# MainBoard.net
KiCad netlist of a schematic drawn in EAGLE
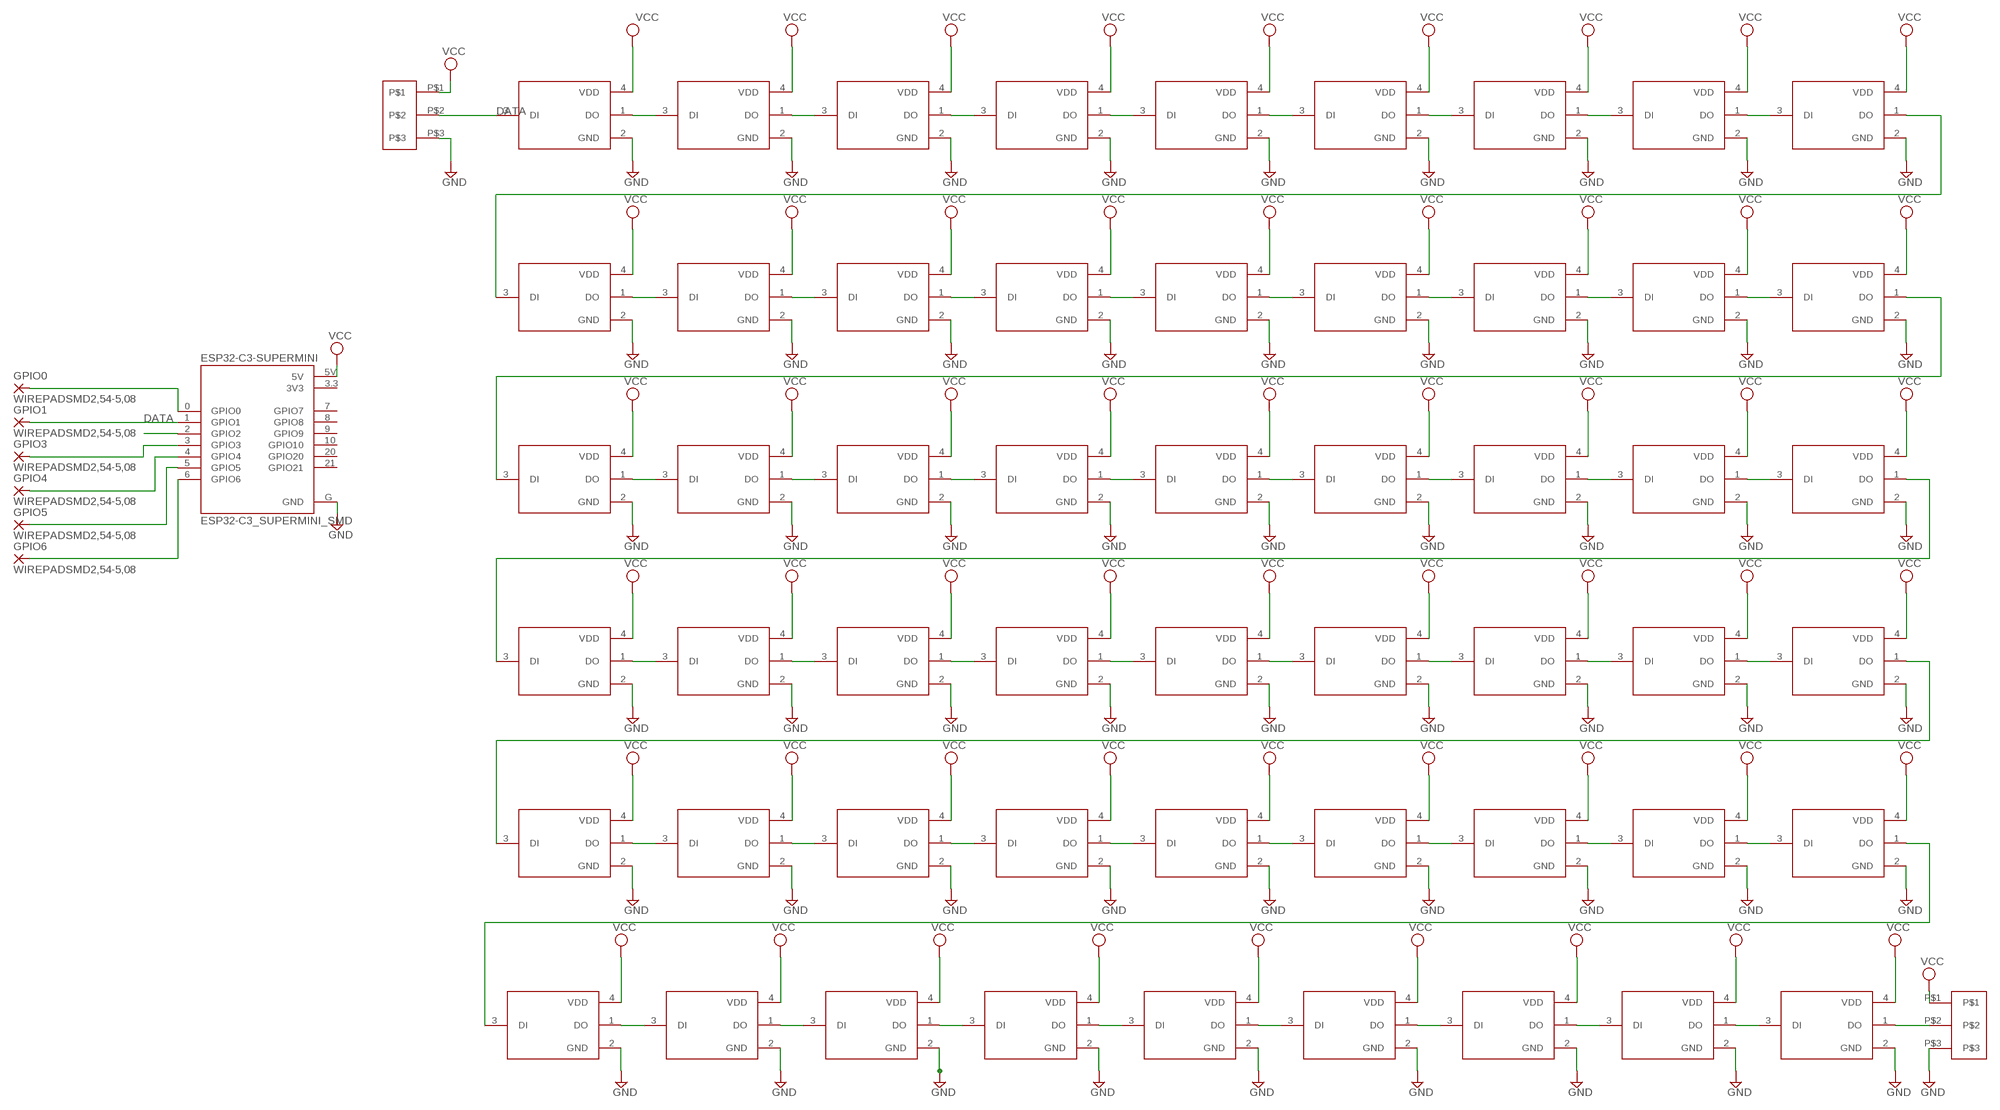
[diagram p0: schematic, sheet 1]

(export (version "E")
  (design (tool "Eeschema 10.0.6"))
  (components
    (comp (ref "ESP32-C3-SUPERMINI")
      (value "ESP32-C3_SUPERMINI_SMD")
      (footprint "eagle-import:MODULE_ESP32-C3_SUPERMINI")
      (fields (field (name "MF") "Espressif Systems") (field (name "MP") "ESP32-C3 SuperMini_SMD"))
      (libsource (lib "eagle-import") (part "ESP32-C3_SUPERMINI_SMD"))
    )
    (comp (ref "GPIO0")
      (value "WIREPADSMD2,54-5,08")
      (footprint "eagle-import:SMD2,54-5,08")
      (libsource (lib "eagle-import") (part "WIREPADSMD2,54-5,08"))
    )
    (comp (ref "GPIO1")
      (value "WIREPADSMD2,54-5,08")
      (footprint "eagle-import:SMD2,54-5,08")
      (libsource (lib "eagle-import") (part "WIREPADSMD2,54-5,08"))
    )
    (comp (ref "GPIO3")
      (value "WIREPADSMD2,54-5,08")
      (footprint "eagle-import:SMD2,54-5,08")
      (libsource (lib "eagle-import") (part "WIREPADSMD2,54-5,08"))
    )
    (comp (ref "GPIO4")
      (value "WIREPADSMD2,54-5,08")
      (footprint "eagle-import:SMD2,54-5,08")
      (libsource (lib "eagle-import") (part "WIREPADSMD2,54-5,08"))
    )
    (comp (ref "GPIO5")
      (value "WIREPADSMD2,54-5,08")
      (footprint "eagle-import:SMD2,54-5,08")
      (libsource (lib "eagle-import") (part "WIREPADSMD2,54-5,08"))
    )
    (comp (ref "GPIO6")
      (value "WIREPADSMD2,54-5,08")
      (footprint "eagle-import:SMD2,54-5,08")
      (libsource (lib "eagle-import") (part "WIREPADSMD2,54-5,08"))
    )
    (comp (ref "LED1")
      (value "WS2812B2020")
      (footprint "eagle-import:LED_WS2812B2020")
      (fields (field (name "MF") "WorldSemi"))
      (libsource (lib "eagle-import") (part "WS2812B2020"))
    )
    (comp (ref "LED2")
      (value "WS2812B2020")
      (footprint "eagle-import:LED_WS2812B2020")
      (fields (field (name "MF") "WorldSemi"))
      (libsource (lib "eagle-import") (part "WS2812B2020"))
    )
    (comp (ref "LED3")
      (value "WS2812B2020")
      (footprint "eagle-import:LED_WS2812B2020")
      (fields (field (name "MF") "WorldSemi"))
      (libsource (lib "eagle-import") (part "WS2812B2020"))
    )
    (comp (ref "LED4")
      (value "WS2812B2020")
      (footprint "eagle-import:LED_WS2812B2020")
      (fields (field (name "MF") "WorldSemi"))
      (libsource (lib "eagle-import") (part "WS2812B2020"))
    )
    (comp (ref "LED5")
      (value "WS2812B2020")
      (footprint "eagle-import:LED_WS2812B2020")
      (fields (field (name "MF") "WorldSemi"))
      (libsource (lib "eagle-import") (part "WS2812B2020"))
    )
    (comp (ref "LED6")
      (value "WS2812B2020")
      (footprint "eagle-import:LED_WS2812B2020")
      (fields (field (name "MF") "WorldSemi"))
      (libsource (lib "eagle-import") (part "WS2812B2020"))
    )
    (comp (ref "LED7")
      (value "WS2812B2020")
      (footprint "eagle-import:LED_WS2812B2020")
      (fields (field (name "MF") "WorldSemi"))
      (libsource (lib "eagle-import") (part "WS2812B2020"))
    )
    (comp (ref "LED8")
      (value "WS2812B2020")
      (footprint "eagle-import:LED_WS2812B2020")
      (fields (field (name "MF") "WorldSemi"))
      (libsource (lib "eagle-import") (part "WS2812B2020"))
    )
    (comp (ref "LED9")
      (value "WS2812B2020")
      (footprint "eagle-import:LED_WS2812B2020")
      (fields (field (name "MF") "WorldSemi"))
      (libsource (lib "eagle-import") (part "WS2812B2020"))
    )
    (comp (ref "LED10")
      (value "WS2812B2020")
      (footprint "eagle-import:LED_WS2812B2020")
      (fields (field (name "MF") "WorldSemi"))
      (libsource (lib "eagle-import") (part "WS2812B2020"))
    )
    (comp (ref "LED11")
      (value "WS2812B2020")
      (footprint "eagle-import:LED_WS2812B2020")
      (fields (field (name "MF") "WorldSemi"))
      (libsource (lib "eagle-import") (part "WS2812B2020"))
    )
    (comp (ref "LED12")
      (value "WS2812B2020")
      (footprint "eagle-import:LED_WS2812B2020")
      (fields (field (name "MF") "WorldSemi"))
      (libsource (lib "eagle-import") (part "WS2812B2020"))
    )
    (comp (ref "LED13")
      (value "WS2812B2020")
      (footprint "eagle-import:LED_WS2812B2020")
      (fields (field (name "MF") "WorldSemi"))
      (libsource (lib "eagle-import") (part "WS2812B2020"))
    )
    (comp (ref "LED14")
      (value "WS2812B2020")
      (footprint "eagle-import:LED_WS2812B2020")
      (fields (field (name "MF") "WorldSemi"))
      (libsource (lib "eagle-import") (part "WS2812B2020"))
    )
    (comp (ref "LED15")
      (value "WS2812B2020")
      (footprint "eagle-import:LED_WS2812B2020")
      (fields (field (name "MF") "WorldSemi"))
      (libsource (lib "eagle-import") (part "WS2812B2020"))
    )
    (comp (ref "LED16")
      (value "WS2812B2020")
      (footprint "eagle-import:LED_WS2812B2020")
      (fields (field (name "MF") "WorldSemi"))
      (libsource (lib "eagle-import") (part "WS2812B2020"))
    )
    (comp (ref "LED17")
      (value "WS2812B2020")
      (footprint "eagle-import:LED_WS2812B2020")
      (fields (field (name "MF") "WorldSemi"))
      (libsource (lib "eagle-import") (part "WS2812B2020"))
    )
    (comp (ref "LED18")
      (value "WS2812B2020")
      (footprint "eagle-import:LED_WS2812B2020")
      (fields (field (name "MF") "WorldSemi"))
      (libsource (lib "eagle-import") (part "WS2812B2020"))
    )
    (comp (ref "LED19")
      (value "WS2812B2020")
      (footprint "eagle-import:LED_WS2812B2020")
      (fields (field (name "MF") "WorldSemi"))
      (libsource (lib "eagle-import") (part "WS2812B2020"))
    )
    (comp (ref "LED20")
      (value "WS2812B2020")
      (footprint "eagle-import:LED_WS2812B2020")
      (fields (field (name "MF") "WorldSemi"))
      (libsource (lib "eagle-import") (part "WS2812B2020"))
    )
    (comp (ref "LED21")
      (value "WS2812B2020")
      (footprint "eagle-import:LED_WS2812B2020")
      (fields (field (name "MF") "WorldSemi"))
      (libsource (lib "eagle-import") (part "WS2812B2020"))
    )
    (comp (ref "LED22")
      (value "WS2812B2020")
      (footprint "eagle-import:LED_WS2812B2020")
      (fields (field (name "MF") "WorldSemi"))
      (libsource (lib "eagle-import") (part "WS2812B2020"))
    )
    (comp (ref "LED23")
      (value "WS2812B2020")
      (footprint "eagle-import:LED_WS2812B2020")
      (fields (field (name "MF") "WorldSemi"))
      (libsource (lib "eagle-import") (part "WS2812B2020"))
    )
    (comp (ref "LED24")
      (value "WS2812B2020")
      (footprint "eagle-import:LED_WS2812B2020")
      (fields (field (name "MF") "WorldSemi"))
      (libsource (lib "eagle-import") (part "WS2812B2020"))
    )
    (comp (ref "LED25")
      (value "WS2812B2020")
      (footprint "eagle-import:LED_WS2812B2020")
      (fields (field (name "MF") "WorldSemi"))
      (libsource (lib "eagle-import") (part "WS2812B2020"))
    )
    (comp (ref "LED26")
      (value "WS2812B2020")
      (footprint "eagle-import:LED_WS2812B2020")
      (fields (field (name "MF") "WorldSemi"))
      (libsource (lib "eagle-import") (part "WS2812B2020"))
    )
    (comp (ref "LED27")
      (value "WS2812B2020")
      (footprint "eagle-import:LED_WS2812B2020")
      (fields (field (name "MF") "WorldSemi"))
      (libsource (lib "eagle-import") (part "WS2812B2020"))
    )
    (comp (ref "LED28")
      (value "WS2812B2020")
      (footprint "eagle-import:LED_WS2812B2020")
      (fields (field (name "MF") "WorldSemi"))
      (libsource (lib "eagle-import") (part "WS2812B2020"))
    )
    (comp (ref "LED29")
      (value "WS2812B2020")
      (footprint "eagle-import:LED_WS2812B2020")
      (fields (field (name "MF") "WorldSemi"))
      (libsource (lib "eagle-import") (part "WS2812B2020"))
    )
    (comp (ref "LED30")
      (value "WS2812B2020")
      (footprint "eagle-import:LED_WS2812B2020")
      (fields (field (name "MF") "WorldSemi"))
      (libsource (lib "eagle-import") (part "WS2812B2020"))
    )
    (comp (ref "LED31")
      (value "WS2812B2020")
      (footprint "eagle-import:LED_WS2812B2020")
      (fields (field (name "MF") "WorldSemi"))
      (libsource (lib "eagle-import") (part "WS2812B2020"))
    )
    (comp (ref "LED32")
      (value "WS2812B2020")
      (footprint "eagle-import:LED_WS2812B2020")
      (fields (field (name "MF") "WorldSemi"))
      (libsource (lib "eagle-import") (part "WS2812B2020"))
    )
    (comp (ref "LED33")
      (value "WS2812B2020")
      (footprint "eagle-import:LED_WS2812B2020")
      (fields (field (name "MF") "WorldSemi"))
      (libsource (lib "eagle-import") (part "WS2812B2020"))
    )
    (comp (ref "LED34")
      (value "WS2812B2020")
      (footprint "eagle-import:LED_WS2812B2020")
      (fields (field (name "MF") "WorldSemi"))
      (libsource (lib "eagle-import") (part "WS2812B2020"))
    )
    (comp (ref "LED35")
      (value "WS2812B2020")
      (footprint "eagle-import:LED_WS2812B2020")
      (fields (field (name "MF") "WorldSemi"))
      (libsource (lib "eagle-import") (part "WS2812B2020"))
    )
    (comp (ref "LED36")
      (value "WS2812B2020")
      (footprint "eagle-import:LED_WS2812B2020")
      (fields (field (name "MF") "WorldSemi"))
      (libsource (lib "eagle-import") (part "WS2812B2020"))
    )
    (comp (ref "LED37")
      (value "WS2812B2020")
      (footprint "eagle-import:LED_WS2812B2020")
      (fields (field (name "MF") "WorldSemi"))
      (libsource (lib "eagle-import") (part "WS2812B2020"))
    )
    (comp (ref "LED38")
      (value "WS2812B2020")
      (footprint "eagle-import:LED_WS2812B2020")
      (fields (field (name "MF") "WorldSemi"))
      (libsource (lib "eagle-import") (part "WS2812B2020"))
    )
    (comp (ref "LED39")
      (value "WS2812B2020")
      (footprint "eagle-import:LED_WS2812B2020")
      (fields (field (name "MF") "WorldSemi"))
      (libsource (lib "eagle-import") (part "WS2812B2020"))
    )
    (comp (ref "LED40")
      (value "WS2812B2020")
      (footprint "eagle-import:LED_WS2812B2020")
      (fields (field (name "MF") "WorldSemi"))
      (libsource (lib "eagle-import") (part "WS2812B2020"))
    )
    (comp (ref "LED41")
      (value "WS2812B2020")
      (footprint "eagle-import:LED_WS2812B2020")
      (fields (field (name "MF") "WorldSemi"))
      (libsource (lib "eagle-import") (part "WS2812B2020"))
    )
    (comp (ref "LED42")
      (value "WS2812B2020")
      (footprint "eagle-import:LED_WS2812B2020")
      (fields (field (name "MF") "WorldSemi"))
      (libsource (lib "eagle-import") (part "WS2812B2020"))
    )
    (comp (ref "LED43")
      (value "WS2812B2020")
      (footprint "eagle-import:LED_WS2812B2020")
      (fields (field (name "MF") "WorldSemi"))
      (libsource (lib "eagle-import") (part "WS2812B2020"))
    )
    (comp (ref "LED44")
      (value "WS2812B2020")
      (footprint "eagle-import:LED_WS2812B2020")
      (fields (field (name "MF") "WorldSemi"))
      (libsource (lib "eagle-import") (part "WS2812B2020"))
    )
    (comp (ref "LED45")
      (value "WS2812B2020")
      (footprint "eagle-import:LED_WS2812B2020")
      (fields (field (name "MF") "WorldSemi"))
      (libsource (lib "eagle-import") (part "WS2812B2020"))
    )
    (comp (ref "LED46")
      (value "WS2812B2020")
      (footprint "eagle-import:LED_WS2812B2020")
      (fields (field (name "MF") "WorldSemi"))
      (libsource (lib "eagle-import") (part "WS2812B2020"))
    )
    (comp (ref "LED47")
      (value "WS2812B2020")
      (footprint "eagle-import:LED_WS2812B2020")
      (fields (field (name "MF") "WorldSemi"))
      (libsource (lib "eagle-import") (part "WS2812B2020"))
    )
    (comp (ref "LED48")
      (value "WS2812B2020")
      (footprint "eagle-import:LED_WS2812B2020")
      (fields (field (name "MF") "WorldSemi"))
      (libsource (lib "eagle-import") (part "WS2812B2020"))
    )
    (comp (ref "LED49")
      (value "WS2812B2020")
      (footprint "eagle-import:LED_WS2812B2020")
      (fields (field (name "MF") "WorldSemi"))
      (libsource (lib "eagle-import") (part "WS2812B2020"))
    )
    (comp (ref "LED50")
      (value "WS2812B2020")
      (footprint "eagle-import:LED_WS2812B2020")
      (fields (field (name "MF") "WorldSemi"))
      (libsource (lib "eagle-import") (part "WS2812B2020"))
    )
    (comp (ref "LED51")
      (value "WS2812B2020")
      (footprint "eagle-import:LED_WS2812B2020")
      (fields (field (name "MF") "WorldSemi"))
      (libsource (lib "eagle-import") (part "WS2812B2020"))
    )
    (comp (ref "LED52")
      (value "WS2812B2020")
      (footprint "eagle-import:LED_WS2812B2020")
      (fields (field (name "MF") "WorldSemi"))
      (libsource (lib "eagle-import") (part "WS2812B2020"))
    )
    (comp (ref "LED53")
      (value "WS2812B2020")
      (footprint "eagle-import:LED_WS2812B2020")
      (fields (field (name "MF") "WorldSemi"))
      (libsource (lib "eagle-import") (part "WS2812B2020"))
    )
    (comp (ref "LED54")
      (value "WS2812B2020")
      (footprint "eagle-import:LED_WS2812B2020")
      (fields (field (name "MF") "WorldSemi"))
      (libsource (lib "eagle-import") (part "WS2812B2020"))
    )
    (comp (ref "U$1")
      (value "POGO-3-M")
      (footprint "eagle-import:POGO-3-M")
      (libsource (lib "eagle-import") (part "POGO-3-M"))
    )
    (comp (ref "U$2")
      (value "POGO-3-F")
      (footprint "eagle-import:POGO-3-F")
      (libsource (lib "eagle-import") (part "POGO-3-F"))
    )
  )
  (nets
    (net (code "1") (name "/3V3") (class "Default")
      (node (ref "ESP32-C3-SUPERMINI") (pin "3.3") (pinfunction "3V3_3.3") (pintype "power_in"))
    )
    (net (code "2") (name "/DATA") (class "Default")
      (node (ref "ESP32-C3-SUPERMINI") (pin "2") (pinfunction "GPIO2_2") (pintype "bidirectional"))
      (node (ref "LED1") (pin "3") (pinfunction "DI_3") (pintype "input"))
      (node (ref "U$2") (pin "P$2") (pinfunction "P$2_P$2") (pintype "bidirectional"))
    )
    (net (code "3") (name "GND") (class "Default")
      (node (ref "ESP32-C3-SUPERMINI") (pin "G") (pinfunction "GND_G") (pintype "power_in"))
      (node (ref "LED1") (pin "2") (pinfunction "GND_2") (pintype "power_in"))
      (node (ref "LED10") (pin "2") (pinfunction "GND_2") (pintype "power_in"))
      (node (ref "LED11") (pin "2") (pinfunction "GND_2") (pintype "power_in"))
      (node (ref "LED12") (pin "2") (pinfunction "GND_2") (pintype "power_in"))
      (node (ref "LED13") (pin "2") (pinfunction "GND_2") (pintype "power_in"))
      (node (ref "LED14") (pin "2") (pinfunction "GND_2") (pintype "power_in"))
      (node (ref "LED15") (pin "2") (pinfunction "GND_2") (pintype "power_in"))
      (node (ref "LED16") (pin "2") (pinfunction "GND_2") (pintype "power_in"))
      (node (ref "LED17") (pin "2") (pinfunction "GND_2") (pintype "power_in"))
      (node (ref "LED18") (pin "2") (pinfunction "GND_2") (pintype "power_in"))
      (node (ref "LED19") (pin "2") (pinfunction "GND_2") (pintype "power_in"))
      (node (ref "LED2") (pin "2") (pinfunction "GND_2") (pintype "power_in"))
      (node (ref "LED20") (pin "2") (pinfunction "GND_2") (pintype "power_in"))
      (node (ref "LED21") (pin "2") (pinfunction "GND_2") (pintype "power_in"))
      (node (ref "LED22") (pin "2") (pinfunction "GND_2") (pintype "power_in"))
      (node (ref "LED23") (pin "2") (pinfunction "GND_2") (pintype "power_in"))
      (node (ref "LED24") (pin "2") (pinfunction "GND_2") (pintype "power_in"))
      (node (ref "LED25") (pin "2") (pinfunction "GND_2") (pintype "power_in"))
      (node (ref "LED26") (pin "2") (pinfunction "GND_2") (pintype "power_in"))
      (node (ref "LED27") (pin "2") (pinfunction "GND_2") (pintype "power_in"))
      (node (ref "LED28") (pin "2") (pinfunction "GND_2") (pintype "power_in"))
      (node (ref "LED29") (pin "2") (pinfunction "GND_2") (pintype "power_in"))
      (node (ref "LED3") (pin "2") (pinfunction "GND_2") (pintype "power_in"))
      (node (ref "LED30") (pin "2") (pinfunction "GND_2") (pintype "power_in"))
      (node (ref "LED31") (pin "2") (pinfunction "GND_2") (pintype "power_in"))
      (node (ref "LED32") (pin "2") (pinfunction "GND_2") (pintype "power_in"))
      (node (ref "LED33") (pin "2") (pinfunction "GND_2") (pintype "power_in"))
      (node (ref "LED34") (pin "2") (pinfunction "GND_2") (pintype "power_in"))
      (node (ref "LED35") (pin "2") (pinfunction "GND_2") (pintype "power_in"))
      (node (ref "LED36") (pin "2") (pinfunction "GND_2") (pintype "power_in"))
      (node (ref "LED37") (pin "2") (pinfunction "GND_2") (pintype "power_in"))
      (node (ref "LED38") (pin "2") (pinfunction "GND_2") (pintype "power_in"))
      (node (ref "LED39") (pin "2") (pinfunction "GND_2") (pintype "power_in"))
      (node (ref "LED4") (pin "2") (pinfunction "GND_2") (pintype "power_in"))
      (node (ref "LED40") (pin "2") (pinfunction "GND_2") (pintype "power_in"))
      (node (ref "LED41") (pin "2") (pinfunction "GND_2") (pintype "power_in"))
      (node (ref "LED42") (pin "2") (pinfunction "GND_2") (pintype "power_in"))
      (node (ref "LED43") (pin "2") (pinfunction "GND_2") (pintype "power_in"))
      (node (ref "LED44") (pin "2") (pinfunction "GND_2") (pintype "power_in"))
      (node (ref "LED45") (pin "2") (pinfunction "GND_2") (pintype "power_in"))
      (node (ref "LED46") (pin "2") (pinfunction "GND_2") (pintype "power_in"))
      (node (ref "LED47") (pin "2") (pinfunction "GND_2") (pintype "power_in"))
      (node (ref "LED48") (pin "2") (pinfunction "GND_2") (pintype "power_in"))
      (node (ref "LED49") (pin "2") (pinfunction "GND_2") (pintype "power_in"))
      (node (ref "LED5") (pin "2") (pinfunction "GND_2") (pintype "power_in"))
      (node (ref "LED50") (pin "2") (pinfunction "GND_2") (pintype "power_in"))
      (node (ref "LED51") (pin "2") (pinfunction "GND_2") (pintype "power_in"))
      (node (ref "LED52") (pin "2") (pinfunction "GND_2") (pintype "power_in"))
      (node (ref "LED53") (pin "2") (pinfunction "GND_2") (pintype "power_in"))
      (node (ref "LED54") (pin "2") (pinfunction "GND_2") (pintype "power_in"))
      (node (ref "LED6") (pin "2") (pinfunction "GND_2") (pintype "power_in"))
      (node (ref "LED7") (pin "2") (pinfunction "GND_2") (pintype "power_in"))
      (node (ref "LED8") (pin "2") (pinfunction "GND_2") (pintype "power_in"))
      (node (ref "LED9") (pin "2") (pinfunction "GND_2") (pintype "power_in"))
      (node (ref "U$1") (pin "P$3") (pinfunction "P$3_P$3") (pintype "bidirectional"))
      (node (ref "U$2") (pin "P$3") (pinfunction "P$3_P$3") (pintype "bidirectional"))
    )
    (net (code "4") (name "Net-(ESP32-C3-SUPERMINI-GPIO0)") (class "Default")
      (node (ref "ESP32-C3-SUPERMINI") (pin "0") (pinfunction "GPIO0_0") (pintype "bidirectional"))
      (node (ref "GPIO0") (pin "1") (pinfunction "P_1") (pintype "passive"))
    )
    (net (code "5") (name "Net-(ESP32-C3-SUPERMINI-GPIO1)") (class "Default")
      (node (ref "ESP32-C3-SUPERMINI") (pin "1") (pinfunction "GPIO1_1") (pintype "bidirectional"))
      (node (ref "GPIO1") (pin "1") (pinfunction "P_1") (pintype "passive"))
    )
    (net (code "6") (name "Net-(ESP32-C3-SUPERMINI-GPIO3)") (class "Default")
      (node (ref "ESP32-C3-SUPERMINI") (pin "3") (pinfunction "GPIO3_3") (pintype "bidirectional"))
      (node (ref "GPIO3") (pin "1") (pinfunction "P_1") (pintype "passive"))
    )
    (net (code "7") (name "Net-(ESP32-C3-SUPERMINI-GPIO4)") (class "Default")
      (node (ref "ESP32-C3-SUPERMINI") (pin "4") (pinfunction "GPIO4_4") (pintype "bidirectional"))
      (node (ref "GPIO4") (pin "1") (pinfunction "P_1") (pintype "passive"))
    )
    (net (code "8") (name "Net-(ESP32-C3-SUPERMINI-GPIO5)") (class "Default")
      (node (ref "ESP32-C3-SUPERMINI") (pin "5") (pinfunction "GPIO5_5") (pintype "bidirectional"))
      (node (ref "GPIO5") (pin "1") (pinfunction "P_1") (pintype "passive"))
    )
    (net (code "9") (name "Net-(ESP32-C3-SUPERMINI-GPIO6)") (class "Default")
      (node (ref "ESP32-C3-SUPERMINI") (pin "6") (pinfunction "GPIO6_6") (pintype "bidirectional"))
      (node (ref "GPIO6") (pin "1") (pinfunction "P_1") (pintype "passive"))
    )
    (net (code "10") (name "Net-(LED1-DO)") (class "Default")
      (node (ref "LED1") (pin "1") (pinfunction "DO_1") (pintype "output"))
      (node (ref "LED2") (pin "3") (pinfunction "DI_3") (pintype "input"))
    )
    (net (code "11") (name "Net-(LED2-DO)") (class "Default")
      (node (ref "LED2") (pin "1") (pinfunction "DO_1") (pintype "output"))
      (node (ref "LED3") (pin "3") (pinfunction "DI_3") (pintype "input"))
    )
    (net (code "12") (name "Net-(LED3-DO)") (class "Default")
      (node (ref "LED3") (pin "1") (pinfunction "DO_1") (pintype "output"))
      (node (ref "LED4") (pin "3") (pinfunction "DI_3") (pintype "input"))
    )
    (net (code "13") (name "Net-(LED4-DO)") (class "Default")
      (node (ref "LED4") (pin "1") (pinfunction "DO_1") (pintype "output"))
      (node (ref "LED5") (pin "3") (pinfunction "DI_3") (pintype "input"))
    )
    (net (code "14") (name "Net-(LED5-DO)") (class "Default")
      (node (ref "LED5") (pin "1") (pinfunction "DO_1") (pintype "output"))
      (node (ref "LED6") (pin "3") (pinfunction "DI_3") (pintype "input"))
    )
    (net (code "15") (name "Net-(LED6-DO)") (class "Default")
      (node (ref "LED6") (pin "1") (pinfunction "DO_1") (pintype "output"))
      (node (ref "LED7") (pin "3") (pinfunction "DI_3") (pintype "input"))
    )
    (net (code "16") (name "Net-(LED7-DO)") (class "Default")
      (node (ref "LED7") (pin "1") (pinfunction "DO_1") (pintype "output"))
      (node (ref "LED8") (pin "3") (pinfunction "DI_3") (pintype "input"))
    )
    (net (code "17") (name "Net-(LED8-DO)") (class "Default")
      (node (ref "LED8") (pin "1") (pinfunction "DO_1") (pintype "output"))
      (node (ref "LED9") (pin "3") (pinfunction "DI_3") (pintype "input"))
    )
    (net (code "18") (name "Net-(LED10-DI)") (class "Default")
      (node (ref "LED10") (pin "3") (pinfunction "DI_3") (pintype "input"))
      (node (ref "LED9") (pin "1") (pinfunction "DO_1") (pintype "output"))
    )
    (net (code "19") (name "Net-(LED10-DO)") (class "Default")
      (node (ref "LED10") (pin "1") (pinfunction "DO_1") (pintype "output"))
      (node (ref "LED11") (pin "3") (pinfunction "DI_3") (pintype "input"))
    )
    (net (code "20") (name "Net-(LED11-DO)") (class "Default")
      (node (ref "LED11") (pin "1") (pinfunction "DO_1") (pintype "output"))
      (node (ref "LED12") (pin "3") (pinfunction "DI_3") (pintype "input"))
    )
    (net (code "21") (name "Net-(LED12-DO)") (class "Default")
      (node (ref "LED12") (pin "1") (pinfunction "DO_1") (pintype "output"))
      (node (ref "LED13") (pin "3") (pinfunction "DI_3") (pintype "input"))
    )
    (net (code "22") (name "Net-(LED13-DO)") (class "Default")
      (node (ref "LED13") (pin "1") (pinfunction "DO_1") (pintype "output"))
      (node (ref "LED14") (pin "3") (pinfunction "DI_3") (pintype "input"))
    )
    (net (code "23") (name "Net-(LED14-DO)") (class "Default")
      (node (ref "LED14") (pin "1") (pinfunction "DO_1") (pintype "output"))
      (node (ref "LED15") (pin "3") (pinfunction "DI_3") (pintype "input"))
    )
    (net (code "24") (name "Net-(LED15-DO)") (class "Default")
      (node (ref "LED15") (pin "1") (pinfunction "DO_1") (pintype "output"))
      (node (ref "LED16") (pin "3") (pinfunction "DI_3") (pintype "input"))
    )
    (net (code "25") (name "Net-(LED16-DO)") (class "Default")
      (node (ref "LED16") (pin "1") (pinfunction "DO_1") (pintype "output"))
      (node (ref "LED17") (pin "3") (pinfunction "DI_3") (pintype "input"))
    )
    (net (code "26") (name "Net-(LED17-DO)") (class "Default")
      (node (ref "LED17") (pin "1") (pinfunction "DO_1") (pintype "output"))
      (node (ref "LED18") (pin "3") (pinfunction "DI_3") (pintype "input"))
    )
    (net (code "27") (name "Net-(LED18-DO)") (class "Default")
      (node (ref "LED18") (pin "1") (pinfunction "DO_1") (pintype "output"))
      (node (ref "LED19") (pin "3") (pinfunction "DI_3") (pintype "input"))
    )
    (net (code "28") (name "Net-(LED19-DO)") (class "Default")
      (node (ref "LED19") (pin "1") (pinfunction "DO_1") (pintype "output"))
      (node (ref "LED20") (pin "3") (pinfunction "DI_3") (pintype "input"))
    )
    (net (code "29") (name "Net-(LED20-DO)") (class "Default")
      (node (ref "LED20") (pin "1") (pinfunction "DO_1") (pintype "output"))
      (node (ref "LED21") (pin "3") (pinfunction "DI_3") (pintype "input"))
    )
    (net (code "30") (name "Net-(LED21-DO)") (class "Default")
      (node (ref "LED21") (pin "1") (pinfunction "DO_1") (pintype "output"))
      (node (ref "LED22") (pin "3") (pinfunction "DI_3") (pintype "input"))
    )
    (net (code "31") (name "Net-(LED22-DO)") (class "Default")
      (node (ref "LED22") (pin "1") (pinfunction "DO_1") (pintype "output"))
      (node (ref "LED23") (pin "3") (pinfunction "DI_3") (pintype "input"))
    )
    (net (code "32") (name "Net-(LED23-DO)") (class "Default")
      (node (ref "LED23") (pin "1") (pinfunction "DO_1") (pintype "output"))
      (node (ref "LED24") (pin "3") (pinfunction "DI_3") (pintype "input"))
    )
    (net (code "33") (name "Net-(LED24-DO)") (class "Default")
      (node (ref "LED24") (pin "1") (pinfunction "DO_1") (pintype "output"))
      (node (ref "LED25") (pin "3") (pinfunction "DI_3") (pintype "input"))
    )
    (net (code "34") (name "Net-(LED25-DO)") (class "Default")
      (node (ref "LED25") (pin "1") (pinfunction "DO_1") (pintype "output"))
      (node (ref "LED26") (pin "3") (pinfunction "DI_3") (pintype "input"))
    )
    (net (code "35") (name "Net-(LED26-DO)") (class "Default")
      (node (ref "LED26") (pin "1") (pinfunction "DO_1") (pintype "output"))
      (node (ref "LED27") (pin "3") (pinfunction "DI_3") (pintype "input"))
    )
    (net (code "36") (name "Net-(LED27-DO)") (class "Default")
      (node (ref "LED27") (pin "1") (pinfunction "DO_1") (pintype "output"))
      (node (ref "LED28") (pin "3") (pinfunction "DI_3") (pintype "input"))
    )
    (net (code "37") (name "Net-(LED28-DO)") (class "Default")
      (node (ref "LED28") (pin "1") (pinfunction "DO_1") (pintype "output"))
      (node (ref "LED29") (pin "3") (pinfunction "DI_3") (pintype "input"))
    )
    (net (code "38") (name "Net-(LED29-DO)") (class "Default")
      (node (ref "LED29") (pin "1") (pinfunction "DO_1") (pintype "output"))
      (node (ref "LED30") (pin "3") (pinfunction "DI_3") (pintype "input"))
    )
    (net (code "39") (name "Net-(LED30-DO)") (class "Default")
      (node (ref "LED30") (pin "1") (pinfunction "DO_1") (pintype "output"))
      (node (ref "LED31") (pin "3") (pinfunction "DI_3") (pintype "input"))
    )
    (net (code "40") (name "Net-(LED31-DO)") (class "Default")
      (node (ref "LED31") (pin "1") (pinfunction "DO_1") (pintype "output"))
      (node (ref "LED32") (pin "3") (pinfunction "DI_3") (pintype "input"))
    )
    (net (code "41") (name "Net-(LED32-DO)") (class "Default")
      (node (ref "LED32") (pin "1") (pinfunction "DO_1") (pintype "output"))
      (node (ref "LED33") (pin "3") (pinfunction "DI_3") (pintype "input"))
    )
    (net (code "42") (name "Net-(LED33-DO)") (class "Default")
      (node (ref "LED33") (pin "1") (pinfunction "DO_1") (pintype "output"))
      (node (ref "LED34") (pin "3") (pinfunction "DI_3") (pintype "input"))
    )
    (net (code "43") (name "Net-(LED34-DO)") (class "Default")
      (node (ref "LED34") (pin "1") (pinfunction "DO_1") (pintype "output"))
      (node (ref "LED35") (pin "3") (pinfunction "DI_3") (pintype "input"))
    )
    (net (code "44") (name "Net-(LED35-DO)") (class "Default")
      (node (ref "LED35") (pin "1") (pinfunction "DO_1") (pintype "output"))
      (node (ref "LED36") (pin "3") (pinfunction "DI_3") (pintype "input"))
    )
    (net (code "45") (name "Net-(LED36-DO)") (class "Default")
      (node (ref "LED36") (pin "1") (pinfunction "DO_1") (pintype "output"))
      (node (ref "LED37") (pin "3") (pinfunction "DI_3") (pintype "input"))
    )
    (net (code "46") (name "Net-(LED37-DO)") (class "Default")
      (node (ref "LED37") (pin "1") (pinfunction "DO_1") (pintype "output"))
      (node (ref "LED38") (pin "3") (pinfunction "DI_3") (pintype "input"))
    )
    (net (code "47") (name "Net-(LED38-DO)") (class "Default")
      (node (ref "LED38") (pin "1") (pinfunction "DO_1") (pintype "output"))
      (node (ref "LED39") (pin "3") (pinfunction "DI_3") (pintype "input"))
    )
    (net (code "48") (name "Net-(LED39-DO)") (class "Default")
      (node (ref "LED39") (pin "1") (pinfunction "DO_1") (pintype "output"))
      (node (ref "LED40") (pin "3") (pinfunction "DI_3") (pintype "input"))
    )
    (net (code "49") (name "Net-(LED40-DO)") (class "Default")
      (node (ref "LED40") (pin "1") (pinfunction "DO_1") (pintype "output"))
      (node (ref "LED41") (pin "3") (pinfunction "DI_3") (pintype "input"))
    )
    (net (code "50") (name "Net-(LED41-DO)") (class "Default")
      (node (ref "LED41") (pin "1") (pinfunction "DO_1") (pintype "output"))
      (node (ref "LED42") (pin "3") (pinfunction "DI_3") (pintype "input"))
    )
    (net (code "51") (name "Net-(LED42-DO)") (class "Default")
      (node (ref "LED42") (pin "1") (pinfunction "DO_1") (pintype "output"))
      (node (ref "LED43") (pin "3") (pinfunction "DI_3") (pintype "input"))
    )
    (net (code "52") (name "Net-(LED43-DO)") (class "Default")
      (node (ref "LED43") (pin "1") (pinfunction "DO_1") (pintype "output"))
      (node (ref "LED44") (pin "3") (pinfunction "DI_3") (pintype "input"))
    )
    (net (code "53") (name "Net-(LED44-DO)") (class "Default")
      (node (ref "LED44") (pin "1") (pinfunction "DO_1") (pintype "output"))
      (node (ref "LED45") (pin "3") (pinfunction "DI_3") (pintype "input"))
    )
    (net (code "54") (name "Net-(LED45-DO)") (class "Default")
      (node (ref "LED45") (pin "1") (pinfunction "DO_1") (pintype "output"))
      (node (ref "LED46") (pin "3") (pinfunction "DI_3") (pintype "input"))
    )
    (net (code "55") (name "Net-(LED46-DO)") (class "Default")
      (node (ref "LED46") (pin "1") (pinfunction "DO_1") (pintype "output"))
      (node (ref "LED47") (pin "3") (pinfunction "DI_3") (pintype "input"))
    )
    (net (code "56") (name "Net-(LED47-DO)") (class "Default")
      (node (ref "LED47") (pin "1") (pinfunction "DO_1") (pintype "output"))
      (node (ref "LED48") (pin "3") (pinfunction "DI_3") (pintype "input"))
    )
    (net (code "57") (name "Net-(LED48-DO)") (class "Default")
      (node (ref "LED48") (pin "1") (pinfunction "DO_1") (pintype "output"))
      (node (ref "LED49") (pin "3") (pinfunction "DI_3") (pintype "input"))
    )
    (net (code "58") (name "Net-(LED49-DO)") (class "Default")
      (node (ref "LED49") (pin "1") (pinfunction "DO_1") (pintype "output"))
      (node (ref "LED50") (pin "3") (pinfunction "DI_3") (pintype "input"))
    )
    (net (code "59") (name "Net-(LED50-DO)") (class "Default")
      (node (ref "LED50") (pin "1") (pinfunction "DO_1") (pintype "output"))
      (node (ref "LED51") (pin "3") (pinfunction "DI_3") (pintype "input"))
    )
    (net (code "60") (name "Net-(LED51-DO)") (class "Default")
      (node (ref "LED51") (pin "1") (pinfunction "DO_1") (pintype "output"))
      (node (ref "LED52") (pin "3") (pinfunction "DI_3") (pintype "input"))
    )
    (net (code "61") (name "Net-(LED52-DO)") (class "Default")
      (node (ref "LED52") (pin "1") (pinfunction "DO_1") (pintype "output"))
      (node (ref "LED53") (pin "3") (pinfunction "DI_3") (pintype "input"))
    )
    (net (code "62") (name "Net-(LED53-DO)") (class "Default")
      (node (ref "LED53") (pin "1") (pinfunction "DO_1") (pintype "output"))
      (node (ref "LED54") (pin "3") (pinfunction "DI_3") (pintype "input"))
    )
    (net (code "63") (name "Net-(LED54-DO)") (class "Default")
      (node (ref "LED54") (pin "1") (pinfunction "DO_1") (pintype "output"))
      (node (ref "U$1") (pin "P$2") (pinfunction "P$2_P$2") (pintype "bidirectional"))
    )
    (net (code "64") (name "VCC") (class "Default")
      (node (ref "ESP32-C3-SUPERMINI") (pin "5V") (pinfunction "5V_5V") (pintype "power_in"))
      (node (ref "LED1") (pin "4") (pinfunction "VDD_4") (pintype "power_in"))
      (node (ref "LED10") (pin "4") (pinfunction "VDD_4") (pintype "power_in"))
      (node (ref "LED11") (pin "4") (pinfunction "VDD_4") (pintype "power_in"))
      (node (ref "LED12") (pin "4") (pinfunction "VDD_4") (pintype "power_in"))
      (node (ref "LED13") (pin "4") (pinfunction "VDD_4") (pintype "power_in"))
      (node (ref "LED14") (pin "4") (pinfunction "VDD_4") (pintype "power_in"))
      (node (ref "LED15") (pin "4") (pinfunction "VDD_4") (pintype "power_in"))
      (node (ref "LED16") (pin "4") (pinfunction "VDD_4") (pintype "power_in"))
      (node (ref "LED17") (pin "4") (pinfunction "VDD_4") (pintype "power_in"))
      (node (ref "LED18") (pin "4") (pinfunction "VDD_4") (pintype "power_in"))
      (node (ref "LED19") (pin "4") (pinfunction "VDD_4") (pintype "power_in"))
      (node (ref "LED2") (pin "4") (pinfunction "VDD_4") (pintype "power_in"))
      (node (ref "LED20") (pin "4") (pinfunction "VDD_4") (pintype "power_in"))
      (node (ref "LED21") (pin "4") (pinfunction "VDD_4") (pintype "power_in"))
      (node (ref "LED22") (pin "4") (pinfunction "VDD_4") (pintype "power_in"))
      (node (ref "LED23") (pin "4") (pinfunction "VDD_4") (pintype "power_in"))
      (node (ref "LED24") (pin "4") (pinfunction "VDD_4") (pintype "power_in"))
      (node (ref "LED25") (pin "4") (pinfunction "VDD_4") (pintype "power_in"))
      (node (ref "LED26") (pin "4") (pinfunction "VDD_4") (pintype "power_in"))
      (node (ref "LED27") (pin "4") (pinfunction "VDD_4") (pintype "power_in"))
      (node (ref "LED28") (pin "4") (pinfunction "VDD_4") (pintype "power_in"))
      (node (ref "LED29") (pin "4") (pinfunction "VDD_4") (pintype "power_in"))
      (node (ref "LED3") (pin "4") (pinfunction "VDD_4") (pintype "power_in"))
      (node (ref "LED30") (pin "4") (pinfunction "VDD_4") (pintype "power_in"))
      (node (ref "LED31") (pin "4") (pinfunction "VDD_4") (pintype "power_in"))
      (node (ref "LED32") (pin "4") (pinfunction "VDD_4") (pintype "power_in"))
      (node (ref "LED33") (pin "4") (pinfunction "VDD_4") (pintype "power_in"))
      (node (ref "LED34") (pin "4") (pinfunction "VDD_4") (pintype "power_in"))
      (node (ref "LED35") (pin "4") (pinfunction "VDD_4") (pintype "power_in"))
      (node (ref "LED36") (pin "4") (pinfunction "VDD_4") (pintype "power_in"))
      (node (ref "LED37") (pin "4") (pinfunction "VDD_4") (pintype "power_in"))
      (node (ref "LED38") (pin "4") (pinfunction "VDD_4") (pintype "power_in"))
      (node (ref "LED39") (pin "4") (pinfunction "VDD_4") (pintype "power_in"))
      (node (ref "LED4") (pin "4") (pinfunction "VDD_4") (pintype "power_in"))
      (node (ref "LED40") (pin "4") (pinfunction "VDD_4") (pintype "power_in"))
      (node (ref "LED41") (pin "4") (pinfunction "VDD_4") (pintype "power_in"))
      (node (ref "LED42") (pin "4") (pinfunction "VDD_4") (pintype "power_in"))
      (node (ref "LED43") (pin "4") (pinfunction "VDD_4") (pintype "power_in"))
      (node (ref "LED44") (pin "4") (pinfunction "VDD_4") (pintype "power_in"))
      (node (ref "LED45") (pin "4") (pinfunction "VDD_4") (pintype "power_in"))
      (node (ref "LED46") (pin "4") (pinfunction "VDD_4") (pintype "power_in"))
      (node (ref "LED47") (pin "4") (pinfunction "VDD_4") (pintype "power_in"))
      (node (ref "LED48") (pin "4") (pinfunction "VDD_4") (pintype "power_in"))
      (node (ref "LED49") (pin "4") (pinfunction "VDD_4") (pintype "power_in"))
      (node (ref "LED5") (pin "4") (pinfunction "VDD_4") (pintype "power_in"))
      (node (ref "LED50") (pin "4") (pinfunction "VDD_4") (pintype "power_in"))
      (node (ref "LED51") (pin "4") (pinfunction "VDD_4") (pintype "power_in"))
      (node (ref "LED52") (pin "4") (pinfunction "VDD_4") (pintype "power_in"))
      (node (ref "LED53") (pin "4") (pinfunction "VDD_4") (pintype "power_in"))
      (node (ref "LED54") (pin "4") (pinfunction "VDD_4") (pintype "power_in"))
      (node (ref "LED6") (pin "4") (pinfunction "VDD_4") (pintype "power_in"))
      (node (ref "LED7") (pin "4") (pinfunction "VDD_4") (pintype "power_in"))
      (node (ref "LED8") (pin "4") (pinfunction "VDD_4") (pintype "power_in"))
      (node (ref "LED9") (pin "4") (pinfunction "VDD_4") (pintype "power_in"))
      (node (ref "U$1") (pin "P$1") (pinfunction "P$1_P$1") (pintype "bidirectional"))
      (node (ref "U$2") (pin "P$1") (pinfunction "P$1_P$1") (pintype "bidirectional"))
    )
    (net (code "65") (name "unconnected-(ESP32-C3-SUPERMINI-GPIO7-Pad7)") (class "Default")
      (node (ref "ESP32-C3-SUPERMINI") (pin "7") (pinfunction "GPIO7_7") (pintype "bidirectional"))
    )
    (net (code "66") (name "unconnected-(ESP32-C3-SUPERMINI-GPIO8-Pad8)") (class "Default")
      (node (ref "ESP32-C3-SUPERMINI") (pin "8") (pinfunction "GPIO8_8") (pintype "bidirectional"))
    )
    (net (code "67") (name "unconnected-(ESP32-C3-SUPERMINI-GPIO9-Pad9)") (class "Default")
      (node (ref "ESP32-C3-SUPERMINI") (pin "9") (pinfunction "GPIO9_9") (pintype "bidirectional"))
    )
    (net (code "68") (name "unconnected-(ESP32-C3-SUPERMINI-GPIO10-Pad10)") (class "Default")
      (node (ref "ESP32-C3-SUPERMINI") (pin "10") (pinfunction "GPIO10_10") (pintype "bidirectional"))
    )
    (net (code "69") (name "unconnected-(ESP32-C3-SUPERMINI-GPIO20-Pad20)") (class "Default")
      (node (ref "ESP32-C3-SUPERMINI") (pin "20") (pinfunction "GPIO20_20") (pintype "bidirectional"))
    )
    (net (code "70") (name "unconnected-(ESP32-C3-SUPERMINI-GPIO21-Pad21)") (class "Default")
      (node (ref "ESP32-C3-SUPERMINI") (pin "21") (pinfunction "GPIO21_21") (pintype "bidirectional"))
    )
  )
)
